# relay.net
KiCad netlist of a schematic drawn in EAGLE
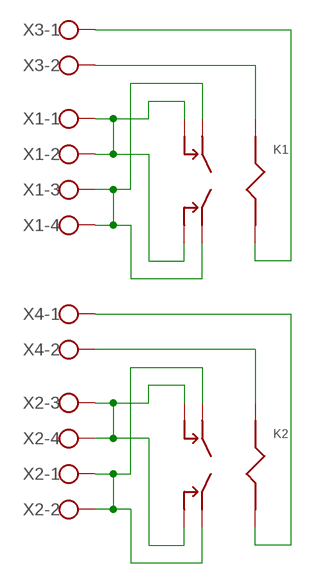
[diagram p0: schematic, sheet 1]

(export (version "E")
  (design (tool "Eeschema 10.0.6"))
  (components
    (comp (ref "K1")
      (value "T92S7D12")
      (footprint "eagle-import:T92-PCPIN")
      (libsource (lib "eagle-import") (part "T92S7D12"))
    )
    (comp (ref "K2")
      (value "T92S7D12")
      (footprint "eagle-import:T92-PCPIN")
      (libsource (lib "eagle-import") (part "T92S7D12"))
    )
    (comp (ref "X1")
      (value "W237-4")
      (footprint "eagle-import:W237-4")
      (libsource (lib "eagle-import") (part "W237-4"))
    )
    (comp (ref "X2")
      (value "W237-4")
      (footprint "eagle-import:W237-4")
      (libsource (lib "eagle-import") (part "W237-4"))
    )
    (comp (ref "X3")
      (value "W237-102")
      (footprint "eagle-import:W237-102")
      (fields (field (name "MPN") "237-102"))
      (libsource (lib "eagle-import") (part "W237-102"))
    )
    (comp (ref "X4")
      (value "W237-102")
      (footprint "eagle-import:W237-102")
      (fields (field (name "MPN") "237-102"))
      (libsource (lib "eagle-import") (part "W237-102"))
    )
  )
  (nets
    (net (code "1") (name "Net-(X1A-KL)") (class "Default")
      (node (ref "K1") (pin "2A") (pinfunction "2_2A") (pintype "bidirectional"))
      (node (ref "K1") (pin "2B") (pinfunction "2_2B") (pintype "bidirectional"))
      (node (ref "K1") (pin "6A") (pinfunction "6_6A") (pintype "bidirectional"))
      (node (ref "K1") (pin "6B") (pinfunction "6_6B") (pintype "bidirectional"))
      (node (ref "X1") (pin "1") (pinfunction "KL_1") (pintype "passive"))
      (node (ref "X1") (pin "2") (pinfunction "KL_2") (pintype "passive"))
    )
    (net (code "2") (name "Net-(X1C-KL)") (class "Default")
      (node (ref "K1") (pin "4A") (pinfunction "4_4A") (pintype "bidirectional"))
      (node (ref "K1") (pin "4B") (pinfunction "4_4B") (pintype "bidirectional"))
      (node (ref "K1") (pin "8A") (pinfunction "8_8A") (pintype "bidirectional"))
      (node (ref "K1") (pin "8B") (pinfunction "8_8B") (pintype "bidirectional"))
      (node (ref "X1") (pin "3") (pinfunction "KL_3") (pintype "passive"))
      (node (ref "X1") (pin "4") (pinfunction "KL_4") (pintype "passive"))
    )
    (net (code "3") (name "Net-(X2A-KL)") (class "Default")
      (node (ref "K2") (pin "4A") (pinfunction "4_4A") (pintype "bidirectional"))
      (node (ref "K2") (pin "4B") (pinfunction "4_4B") (pintype "bidirectional"))
      (node (ref "K2") (pin "8A") (pinfunction "8_8A") (pintype "bidirectional"))
      (node (ref "K2") (pin "8B") (pinfunction "8_8B") (pintype "bidirectional"))
      (node (ref "X2") (pin "1") (pinfunction "KL_1") (pintype "passive"))
      (node (ref "X2") (pin "2") (pinfunction "KL_2") (pintype "passive"))
    )
    (net (code "4") (name "Net-(X2C-KL)") (class "Default")
      (node (ref "K2") (pin "2A") (pinfunction "2_2A") (pintype "bidirectional"))
      (node (ref "K2") (pin "2B") (pinfunction "2_2B") (pintype "bidirectional"))
      (node (ref "K2") (pin "6A") (pinfunction "6_6A") (pintype "bidirectional"))
      (node (ref "K2") (pin "6B") (pinfunction "6_6B") (pintype "bidirectional"))
      (node (ref "X2") (pin "3") (pinfunction "KL_3") (pintype "passive"))
      (node (ref "X2") (pin "4") (pinfunction "KL_4") (pintype "passive"))
    )
    (net (code "5") (name "Net-(X3A-KL)") (class "Default")
      (node (ref "K1") (pin "1A") (pinfunction "1_1A") (pintype "bidirectional"))
      (node (ref "K1") (pin "1B") (pinfunction "1_1B") (pintype "bidirectional"))
      (node (ref "X3") (pin "1") (pinfunction "KL_1") (pintype "passive"))
    )
    (net (code "6") (name "Net-(X3B-KL)") (class "Default")
      (node (ref "K1") (pin "0A") (pinfunction "0_0A") (pintype "bidirectional"))
      (node (ref "K1") (pin "0B") (pinfunction "0_0B") (pintype "bidirectional"))
      (node (ref "X3") (pin "2") (pinfunction "KL_2") (pintype "passive"))
    )
    (net (code "7") (name "Net-(X4A-KL)") (class "Default")
      (node (ref "K2") (pin "1A") (pinfunction "1_1A") (pintype "bidirectional"))
      (node (ref "K2") (pin "1B") (pinfunction "1_1B") (pintype "bidirectional"))
      (node (ref "X4") (pin "1") (pinfunction "KL_1") (pintype "passive"))
    )
    (net (code "8") (name "Net-(X4B-KL)") (class "Default")
      (node (ref "K2") (pin "0A") (pinfunction "0_0A") (pintype "bidirectional"))
      (node (ref "K2") (pin "0B") (pinfunction "0_0B") (pintype "bidirectional"))
      (node (ref "X4") (pin "2") (pinfunction "KL_2") (pintype "passive"))
    )
  )
)
